# IdealDiode.net
KiCad netlist of a schematic drawn in Altium Designer
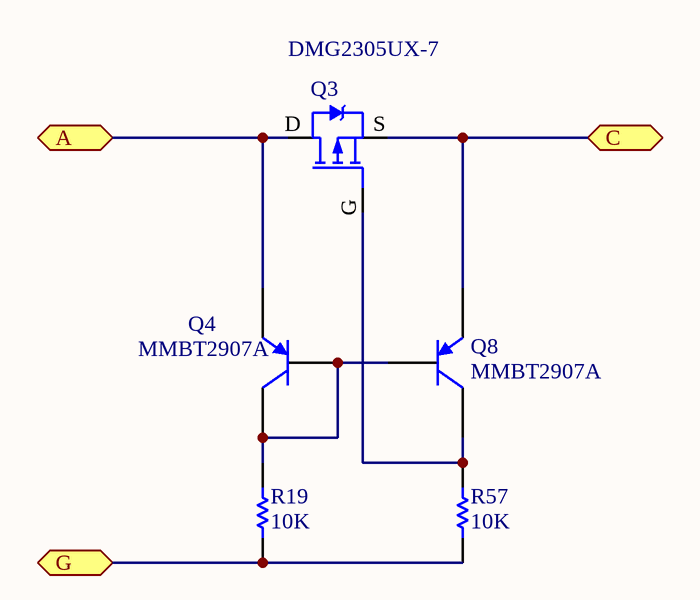
[diagram p0: IdealDiode.SchDoc]

(export (version "E")
  (design (tool "Eeschema 10.0.6"))
  (components
    (comp (ref "Q3")
      (value "DMG2305UX")
      (footprint "DMG2305UX-7")
      (description "MOSFET P-CH 20V 4.2A SOT23")
      (fields
        (field (name "MANUFACTURER") "Diodes Incorporated")
        (field (name "MANUFACTURER PART NUMBER") "DMG2305UX-7")
        (field (name "CREATOR") "osman")
      )
      (libsource (lib "OLogic-Trans-Drivers") (part "DMG2305UX"))
    )
    (comp (ref "Q4")
      (value "MMBT2907A")
      (footprint "SOT23")
      (description "PNP General Purpose Amplifier")
      (fields (field (name "MANUFACTURER") "Fairchild Semiconductor"))
      (libsource (lib "OLogic-Trans-Drivers") (part "MMBT2907A"))
    )
    (comp (ref "Q8")
      (value "MMBT2907A")
      (footprint "SOT23")
      (description "PNP General Purpose Amplifier")
      (fields (field (name "MANUFACTURER") "Fairchild Semiconductor"))
      (libsource (lib "OLogic-Trans-Drivers") (part "MMBT2907A"))
    )
    (comp (ref "R19")
      (value "10K")
      (footprint "RESC0402(1005)_N")
      (description "10K 0402")
      (fields
        (field (name "MANUFACTURER") "Panasonic Electronic Components")
        (field (name "MANUFACTURER PART NUMBER") "ERJ-2GEJ103X")
        (field (name "CREATOR") "ted")
      )
      (libsource (lib "OLogic-Passive") (part "RES 10K OHM 5% 1/10W 0402"))
    )
    (comp (ref "R57")
      (value "10K")
      (footprint "RESC0402(1005)_N")
      (description "10K 0402")
      (fields
        (field (name "MANUFACTURER") "Panasonic Electronic Components")
        (field (name "MANUFACTURER PART NUMBER") "ERJ-2GEJ103X")
        (field (name "CREATOR") "ted")
      )
      (libsource (lib "OLogic-Passive") (part "RES 10K OHM 5% 1/10W 0402"))
    )
  )
  (nets
    (net (code "1") (name "/A") (class "Default")
      (node (ref "Q3") (pin "D") (pinfunction "D_D") (pintype "passive"))
      (node (ref "Q4") (pin "2") (pinfunction "E_2") (pintype "passive"))
    )
    (net (code "2") (name "/C") (class "Default")
      (node (ref "Q3") (pin "S") (pinfunction "S_S") (pintype "passive"))
      (node (ref "Q8") (pin "2") (pinfunction "E_2") (pintype "passive"))
    )
    (net (code "3") (name "/G") (class "Default")
      (node (ref "R19") (pin "1") (pinfunction "1_1") (pintype "passive"))
      (node (ref "R57") (pin "1") (pinfunction "1_1") (pintype "passive"))
    )
    (net (code "4") (name "Net-(Q4-B)") (class "Default")
      (node (ref "Q4") (pin "1") (pinfunction "B_1") (pintype "passive"))
      (node (ref "Q4") (pin "3") (pinfunction "C_3") (pintype "passive"))
      (node (ref "Q8") (pin "1") (pinfunction "B_1") (pintype "passive"))
      (node (ref "R19") (pin "2") (pinfunction "2_2") (pintype "passive"))
    )
    (net (code "5") (name "Net-(Q8-C)") (class "Default")
      (node (ref "Q3") (pin "G") (pinfunction "G_G") (pintype "passive"))
      (node (ref "Q8") (pin "3") (pinfunction "C_3") (pintype "passive"))
      (node (ref "R57") (pin "2") (pinfunction "2_2") (pintype "passive"))
    )
  )
)
